# stm32f103c8t6.net
KiCad netlist of a schematic drawn in EAGLE
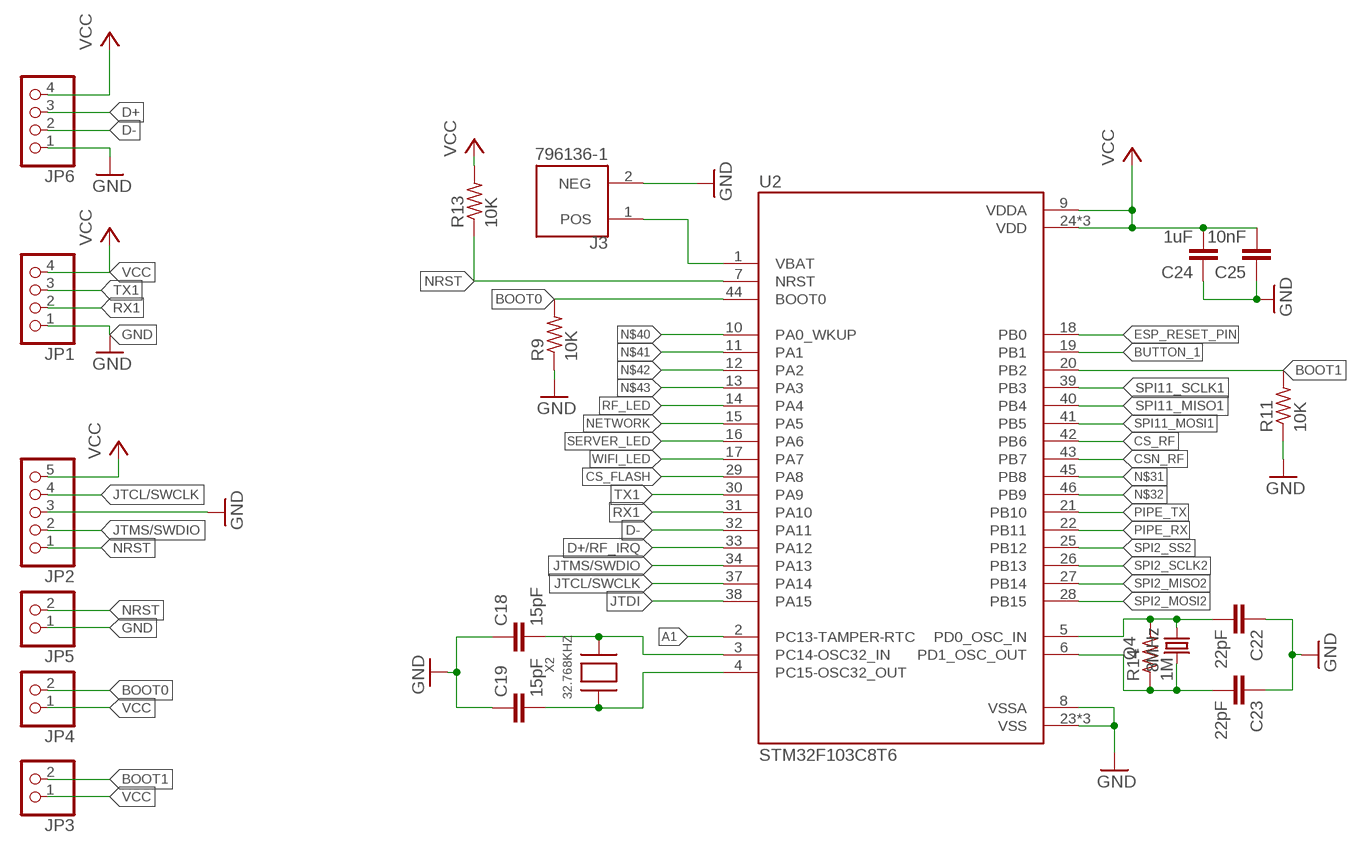
[diagram p0: schematic, sheet 1]

(export (version "E")
  (design (tool "Eeschema 10.0.6"))
  (components
    (comp (ref "C18")
      (value "15pF")
      (footprint "eagle-import:C0603")
      (libsource (lib "eagle-import") (part "C-EUC0603"))
    )
    (comp (ref "C19")
      (value "15pF")
      (footprint "eagle-import:C0603")
      (libsource (lib "eagle-import") (part "C-EUC0603"))
    )
    (comp (ref "C22")
      (value "22pF")
      (footprint "eagle-import:C0603")
      (libsource (lib "eagle-import") (part "C-EUC0603"))
    )
    (comp (ref "C23")
      (value "22pF")
      (footprint "eagle-import:C0603")
      (libsource (lib "eagle-import") (part "C-EUC0603"))
    )
    (comp (ref "C24")
      (value "1uF")
      (footprint "eagle-import:C0603")
      (libsource (lib "eagle-import") (part "C-EUC0603"))
    )
    (comp (ref "C25")
      (value "10nF")
      (footprint "eagle-import:C0603")
      (libsource (lib "eagle-import") (part "C-EUC0603"))
    )
    (comp (ref "J3")
      (value "796136-1")
      (footprint "eagle-import:TE_796136-1")
      (fields (field (name "MF") "TE Connectivity"))
      (libsource (lib "eagle-import") (part "796136-1"))
    )
    (comp (ref "JP1")
      (value "PINHD-1X4")
      (footprint "eagle-import:1X04")
      (libsource (lib "eagle-import") (part "PINHD-1X4"))
    )
    (comp (ref "JP2")
      (value "PINHD-1X5")
      (footprint "eagle-import:1X05")
      (libsource (lib "eagle-import") (part "PINHD-1X5"))
    )
    (comp (ref "JP3")
      (value "PINHD-1X2")
      (footprint "eagle-import:1X02")
      (libsource (lib "eagle-import") (part "PINHD-1X2"))
    )
    (comp (ref "JP4")
      (value "PINHD-1X2")
      (footprint "eagle-import:1X02")
      (libsource (lib "eagle-import") (part "PINHD-1X2"))
    )
    (comp (ref "JP5")
      (value "PINHD-1X2")
      (footprint "eagle-import:1X02")
      (libsource (lib "eagle-import") (part "PINHD-1X2"))
    )
    (comp (ref "JP6")
      (value "PINHD-1X4")
      (footprint "eagle-import:1X04")
      (libsource (lib "eagle-import") (part "PINHD-1X4"))
    )
    (comp (ref "Q4")
      (value "8MHz")
      (footprint "eagle-import:3.2X2.5_KX-7")
      (libsource (lib "eagle-import") (part "KX-7"))
    )
    (comp (ref "R9")
      (value "10K")
      (footprint "eagle-import:R0603")
      (libsource (lib "eagle-import") (part "R-US_R0603"))
    )
    (comp (ref "R11")
      (value "10K")
      (footprint "eagle-import:R0603")
      (libsource (lib "eagle-import") (part "R-US_R0603"))
    )
    (comp (ref "R13")
      (value "10K")
      (footprint "eagle-import:R0603")
      (libsource (lib "eagle-import") (part "R-US_R0603"))
    )
    (comp (ref "R14")
      (value "1M")
      (footprint "eagle-import:R0603")
      (libsource (lib "eagle-import") (part "R-US_R0603"))
    )
    (comp (ref "U2")
      (value "STM32F103C8T6")
      (footprint "eagle-import:QFP50P900X900X160-48N")
      (fields (field (name "MF") "STMicroelectronics"))
      (libsource (lib "eagle-import") (part "STM32F103C8T6"))
    )
    (comp (ref "X2")
      (value "32.768KHZ")
      (footprint "eagle-import:XTAL3215")
      (libsource (lib "eagle-import") (part "XTAL-3.2X1.5"))
    )
  )
  (nets
    (net (code "1") (name "A1") (class "Default")
      (node (ref "U2") (pin "2") (pinfunction "PC13-TAMPER-RTC_2") (pintype "bidirectional"))
    )
    (net (code "2") (name "BOOT0") (class "Default")
      (node (ref "JP4") (pin "2") (pinfunction "2_2") (pintype "passive"))
      (node (ref "R9") (pin "2") (pinfunction "2_2") (pintype "passive"))
      (node (ref "U2") (pin "44") (pinfunction "BOOT0_44") (pintype "input"))
    )
    (net (code "3") (name "BOOT1") (class "Default")
      (node (ref "JP3") (pin "2") (pinfunction "2_2") (pintype "passive"))
      (node (ref "R11") (pin "2") (pinfunction "2_2") (pintype "passive"))
      (node (ref "U2") (pin "20") (pinfunction "PB2_20") (pintype "bidirectional"))
    )
    (net (code "4") (name "BUTTON_1") (class "Default")
      (node (ref "U2") (pin "19") (pinfunction "PB1_19") (pintype "bidirectional"))
    )
    (net (code "5") (name "CSN_RF") (class "Default")
      (node (ref "U2") (pin "43") (pinfunction "PB7_43") (pintype "bidirectional"))
    )
    (net (code "6") (name "CS_FLASH") (class "Default")
      (node (ref "U2") (pin "29") (pinfunction "PA8_29") (pintype "bidirectional"))
    )
    (net (code "7") (name "CS_RF") (class "Default")
      (node (ref "U2") (pin "42") (pinfunction "PB6_42") (pintype "bidirectional"))
    )
    (net (code "8") (name "D+") (class "Default")
      (node (ref "JP6") (pin "3") (pinfunction "3_3") (pintype "passive"))
    )
    (net (code "9") (name "D+{slash}RF_IRQ") (class "Default")
      (node (ref "U2") (pin "33") (pinfunction "PA12_33") (pintype "bidirectional"))
    )
    (net (code "10") (name "D-") (class "Default")
      (node (ref "JP6") (pin "2") (pinfunction "2_2") (pintype "passive"))
      (node (ref "U2") (pin "32") (pinfunction "PA11_32") (pintype "bidirectional"))
    )
    (net (code "11") (name "ESP_RESET_PIN") (class "Default")
      (node (ref "U2") (pin "18") (pinfunction "PB0_18") (pintype "bidirectional"))
    )
    (net (code "12") (name "GND") (class "Default")
      (node (ref "C18") (pin "1") (pinfunction "1_1") (pintype "passive"))
      (node (ref "C19") (pin "1") (pinfunction "1_1") (pintype "passive"))
      (node (ref "C22") (pin "1") (pinfunction "1_1") (pintype "passive"))
      (node (ref "C23") (pin "1") (pinfunction "1_1") (pintype "passive"))
      (node (ref "C24") (pin "1") (pinfunction "1_1") (pintype "passive"))
      (node (ref "C25") (pin "1") (pinfunction "1_1") (pintype "passive"))
      (node (ref "J3") (pin "2") (pinfunction "NEG_2") (pintype "passive"))
      (node (ref "JP1") (pin "1") (pinfunction "1_1") (pintype "passive"))
      (node (ref "JP2") (pin "3") (pinfunction "3_3") (pintype "passive"))
      (node (ref "JP5") (pin "1") (pinfunction "1_1") (pintype "passive"))
      (node (ref "JP6") (pin "1") (pinfunction "1_1") (pintype "passive"))
      (node (ref "R11") (pin "1") (pinfunction "1_1") (pintype "passive"))
      (node (ref "R9") (pin "1") (pinfunction "1_1") (pintype "passive"))
      (node (ref "U2") (pin "23") (pinfunction "VSS_23") (pintype "power_in"))
      (node (ref "U2") (pin "35") (pinfunction "VSS_35") (pintype "power_in"))
      (node (ref "U2") (pin "47") (pinfunction "VSS_47") (pintype "power_in"))
      (node (ref "U2") (pin "8") (pinfunction "VSSA_8") (pintype "power_in"))
    )
    (net (code "13") (name "JTCL{slash}SWCLK") (class "Default")
      (node (ref "JP2") (pin "4") (pinfunction "4_4") (pintype "passive"))
      (node (ref "U2") (pin "37") (pinfunction "PA14_37") (pintype "bidirectional"))
    )
    (net (code "14") (name "JTDI") (class "Default")
      (node (ref "U2") (pin "38") (pinfunction "PA15_38") (pintype "bidirectional"))
    )
    (net (code "15") (name "JTMS{slash}SWDIO") (class "Default")
      (node (ref "JP2") (pin "2") (pinfunction "2_2") (pintype "passive"))
      (node (ref "U2") (pin "34") (pinfunction "PA13_34") (pintype "bidirectional"))
    )
    (net (code "16") (name "N$31") (class "Default")
      (node (ref "C22") (pin "2") (pinfunction "2_2") (pintype "passive"))
      (node (ref "Q4") (pin "1") (pinfunction "1_1") (pintype "passive"))
      (node (ref "R14") (pin "2") (pinfunction "2_2") (pintype "passive"))
      (node (ref "U2") (pin "45") (pinfunction "PB8_45") (pintype "bidirectional"))
      (node (ref "U2") (pin "5") (pinfunction "PD0_OSC_IN_5") (pintype "bidirectional"))
    )
    (net (code "17") (name "N$32") (class "Default")
      (node (ref "J3") (pin "1") (pinfunction "POS_1") (pintype "passive"))
      (node (ref "U2") (pin "1") (pinfunction "VBAT_1") (pintype "bidirectional"))
      (node (ref "U2") (pin "46") (pinfunction "PB9_46") (pintype "bidirectional"))
    )
    (net (code "18") (name "N$40") (class "Default")
      (node (ref "U2") (pin "10") (pinfunction "PA0_WKUP_10") (pintype "bidirectional"))
    )
    (net (code "19") (name "N$41") (class "Default")
      (node (ref "U2") (pin "11") (pinfunction "PA1_11") (pintype "bidirectional"))
    )
    (net (code "20") (name "N$42") (class "Default")
      (node (ref "U2") (pin "12") (pinfunction "PA2_12") (pintype "bidirectional"))
    )
    (net (code "21") (name "N$43") (class "Default")
      (node (ref "U2") (pin "13") (pinfunction "PA3_13") (pintype "bidirectional"))
    )
    (net (code "22") (name "NETWORK") (class "Default")
      (node (ref "U2") (pin "15") (pinfunction "PA5_15") (pintype "bidirectional"))
    )
    (net (code "23") (name "NRST") (class "Default")
      (node (ref "JP2") (pin "1") (pinfunction "1_1") (pintype "passive"))
      (node (ref "JP5") (pin "2") (pinfunction "2_2") (pintype "passive"))
      (node (ref "R13") (pin "1") (pinfunction "1_1") (pintype "passive"))
      (node (ref "U2") (pin "7") (pinfunction "NRST_7") (pintype "input"))
    )
    (net (code "24") (name "Net-(Q4-2)") (class "Default")
      (node (ref "C23") (pin "2") (pinfunction "2_2") (pintype "passive"))
      (node (ref "Q4") (pin "3") (pinfunction "2_3") (pintype "passive"))
      (node (ref "R14") (pin "1") (pinfunction "1_1") (pintype "passive"))
      (node (ref "U2") (pin "6") (pinfunction "PD1_OSC_OUT_6") (pintype "bidirectional"))
    )
    (net (code "25") (name "Net-(U2-PC14-OSC32_IN)") (class "Default")
      (node (ref "C18") (pin "2") (pinfunction "2_2") (pintype "passive"))
      (node (ref "U2") (pin "3") (pinfunction "PC14-OSC32_IN_3") (pintype "bidirectional"))
      (node (ref "X2") (pin "P$2") (pinfunction "P$2_P$2") (pintype "bidirectional"))
    )
    (net (code "26") (name "Net-(U2-PC15-OSC32_OUT)") (class "Default")
      (node (ref "C19") (pin "2") (pinfunction "2_2") (pintype "passive"))
      (node (ref "U2") (pin "4") (pinfunction "PC15-OSC32_OUT_4") (pintype "bidirectional"))
      (node (ref "X2") (pin "P$1") (pinfunction "P$1_P$1") (pintype "bidirectional"))
    )
    (net (code "27") (name "PIPE_RX") (class "Default")
      (node (ref "U2") (pin "22") (pinfunction "PB11_22") (pintype "bidirectional"))
    )
    (net (code "28") (name "PIPE_TX") (class "Default")
      (node (ref "U2") (pin "21") (pinfunction "PB10_21") (pintype "bidirectional"))
    )
    (net (code "29") (name "RF_LED") (class "Default")
      (node (ref "U2") (pin "14") (pinfunction "PA4_14") (pintype "bidirectional"))
    )
    (net (code "30") (name "RX1") (class "Default")
      (node (ref "JP1") (pin "2") (pinfunction "2_2") (pintype "passive"))
      (node (ref "U2") (pin "31") (pinfunction "PA10_31") (pintype "bidirectional"))
    )
    (net (code "31") (name "SERVER_LED") (class "Default")
      (node (ref "U2") (pin "16") (pinfunction "PA6_16") (pintype "bidirectional"))
    )
    (net (code "32") (name "SPI2_MISO2") (class "Default")
      (node (ref "U2") (pin "27") (pinfunction "PB14_27") (pintype "bidirectional"))
    )
    (net (code "33") (name "SPI2_MOSI2") (class "Default")
      (node (ref "U2") (pin "28") (pinfunction "PB15_28") (pintype "bidirectional"))
    )
    (net (code "34") (name "SPI2_SCLK2") (class "Default")
      (node (ref "U2") (pin "26") (pinfunction "PB13_26") (pintype "bidirectional"))
    )
    (net (code "35") (name "SPI2_SS2") (class "Default")
      (node (ref "U2") (pin "25") (pinfunction "PB12_25") (pintype "bidirectional"))
    )
    (net (code "36") (name "SPI11_MISO1") (class "Default")
      (node (ref "U2") (pin "40") (pinfunction "PB4_40") (pintype "bidirectional"))
    )
    (net (code "37") (name "SPI11_MOSI1") (class "Default")
      (node (ref "U2") (pin "41") (pinfunction "PB5_41") (pintype "bidirectional"))
    )
    (net (code "38") (name "SPI11_SCLK1") (class "Default")
      (node (ref "U2") (pin "39") (pinfunction "PB3_39") (pintype "bidirectional"))
    )
    (net (code "39") (name "TX1") (class "Default")
      (node (ref "JP1") (pin "3") (pinfunction "3_3") (pintype "passive"))
      (node (ref "U2") (pin "30") (pinfunction "PA9_30") (pintype "bidirectional"))
    )
    (net (code "40") (name "VCC") (class "Default")
      (node (ref "C24") (pin "2") (pinfunction "2_2") (pintype "passive"))
      (node (ref "C25") (pin "2") (pinfunction "2_2") (pintype "passive"))
      (node (ref "JP1") (pin "4") (pinfunction "4_4") (pintype "passive"))
      (node (ref "JP2") (pin "5") (pinfunction "5_5") (pintype "passive"))
      (node (ref "JP3") (pin "1") (pinfunction "1_1") (pintype "passive"))
      (node (ref "JP4") (pin "1") (pinfunction "1_1") (pintype "passive"))
      (node (ref "JP6") (pin "4") (pinfunction "4_4") (pintype "passive"))
      (node (ref "R13") (pin "2") (pinfunction "2_2") (pintype "passive"))
      (node (ref "U2") (pin "24") (pinfunction "VDD_24") (pintype "power_in"))
      (node (ref "U2") (pin "36") (pinfunction "VDD_36") (pintype "power_in"))
      (node (ref "U2") (pin "48") (pinfunction "VDD_48") (pintype "power_in"))
      (node (ref "U2") (pin "9") (pinfunction "VDDA_9") (pintype "power_in"))
    )
    (net (code "41") (name "WIFI_LED") (class "Default")
      (node (ref "U2") (pin "17") (pinfunction "PA7_17") (pintype "bidirectional"))
    )
  )
)
